# macplus.net
KiCad netlist of a schematic drawn in EAGLE
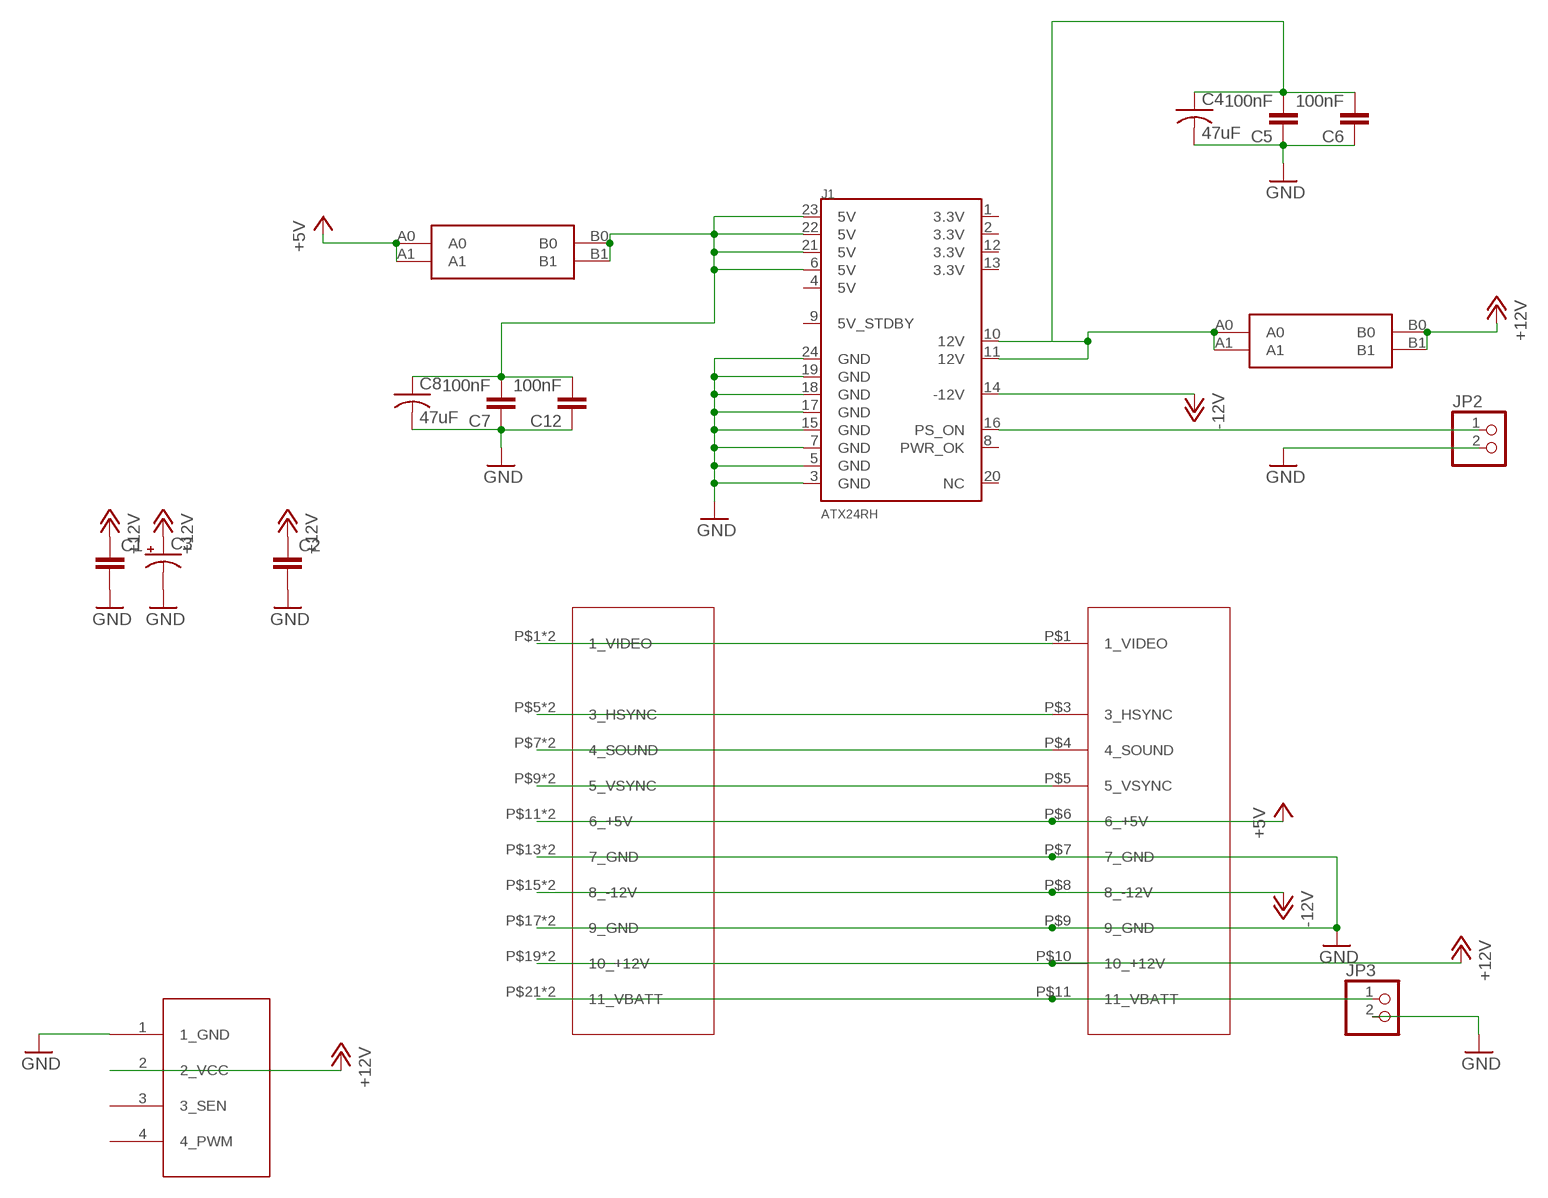
[diagram p0: schematic, sheet 1]

(export (version "E")
  (design (tool "Eeschema 10.0.6"))
  (components
    (comp (ref "C1")
      (value "C5/2.5")
      (footprint "eagle-import:C5B2.5")
      (libsource (lib "eagle-import") (part "C5/2.5"))
    )
    (comp (ref "C2")
      (value "C5/2.5")
      (footprint "eagle-import:C5B2.5")
      (libsource (lib "eagle-import") (part "C5/2.5"))
    )
    (comp (ref "C3")
      (value "CPOL-USE3.5-8")
      (footprint "eagle-import:E3,5-8")
      (libsource (lib "eagle-import") (part "CPOL-USE3.5-8"))
    )
    (comp (ref "C4")
      (value "47uF")
      (footprint "eagle-import:C1210")
      (libsource (lib "eagle-import") (part "C-USC1210"))
    )
    (comp (ref "C5")
      (value "100nF")
      (footprint "eagle-import:0805@1")
      (libsource (lib "eagle-import") (part "CAP0805"))
    )
    (comp (ref "C6")
      (value "100nF")
      (footprint "eagle-import:0805@1")
      (libsource (lib "eagle-import") (part "CAP0805"))
    )
    (comp (ref "C7")
      (value "100nF")
      (footprint "eagle-import:0805@1")
      (libsource (lib "eagle-import") (part "CAP0805"))
    )
    (comp (ref "C8")
      (value "47uF")
      (footprint "eagle-import:C1210")
      (libsource (lib "eagle-import") (part "C-USC1210"))
    )
    (comp (ref "C12")
      (value "100nF")
      (footprint "eagle-import:0805@1")
      (libsource (lib "eagle-import") (part "CAP0805"))
    )
    (comp (ref "J1")
      (value "ATX24RH")
      (footprint "eagle-import:ATX24_STRAIGHT")
      (libsource (lib "eagle-import") (part "ATX24RH"))
    )
    (comp (ref "JP1")
      (value "4PIN_FAN")
      (footprint "eagle-import:1X04")
      (libsource (lib "eagle-import") (part "4PIN_FAN"))
    )
    (comp (ref "JP2")
      (value "PINHD-1X2")
      (footprint "eagle-import:1X02")
      (libsource (lib "eagle-import") (part "PINHD-1X2"))
    )
    (comp (ref "JP3")
      (value "PINHD-1X2")
      (footprint "eagle-import:1X02")
      (libsource (lib "eagle-import") (part "PINHD-1X2"))
    )
    (comp (ref "U$1")
      (value "MACPLUS")
      (footprint "eagle-import:396_10P")
      (libsource (lib "eagle-import") (part "MACPLUS"))
    )
    (comp (ref "U$2")
      (value "CAR_FUSE_HOLDER3IN1")
      (footprint "eagle-import:FUSE_HOLDER_3IN1")
      (libsource (lib "eagle-import") (part "CAR_FUSE_HOLDER3IN1"))
    )
    (comp (ref "U$3")
      (value "3.96_FEM")
      (footprint "eagle-import:3.96_FEMALE_GAP")
      (libsource (lib "eagle-import") (part "3.96_FEM"))
    )
    (comp (ref "U$8")
      (value "CAR_FUSE_HOLDER3IN1")
      (footprint "eagle-import:FUSE_HOLDER_3IN1")
      (libsource (lib "eagle-import") (part "CAR_FUSE_HOLDER3IN1"))
    )
  )
  (nets
    (net (code "1") (name "+5V") (class "Default")
      (node (ref "U$1") (pin "P$6") (pinfunction "6_+5V_P$6") (pintype "bidirectional"))
      (node (ref "U$3") (pin "P$11") (pinfunction "6_+5V_P$11") (pintype "bidirectional"))
      (node (ref "U$3") (pin "P$12") (pinfunction "6_+5V_P$12") (pintype "bidirectional"))
      (node (ref "U$8") (pin "A0") (pinfunction "A0_A0") (pintype "bidirectional"))
      (node (ref "U$8") (pin "A1") (pinfunction "A1_A1") (pintype "bidirectional"))
    )
    (net (code "2") (name "+12V") (class "Default")
      (node (ref "C1") (pin "1") (pinfunction "1_1") (pintype "passive"))
      (node (ref "C2") (pin "1") (pinfunction "1_1") (pintype "passive"))
      (node (ref "C3") (pin "+") (pinfunction "+_+") (pintype "passive"))
      (node (ref "JP1") (pin "2") (pinfunction "2_VCC_2") (pintype "passive"))
      (node (ref "U$1") (pin "P$10") (pinfunction "10_+12V_P$10") (pintype "bidirectional"))
      (node (ref "U$2") (pin "B0") (pinfunction "B0_B0") (pintype "bidirectional"))
      (node (ref "U$2") (pin "B1") (pinfunction "B1_B1") (pintype "bidirectional"))
      (node (ref "U$3") (pin "P$19") (pinfunction "10_+12V_P$19") (pintype "bidirectional"))
      (node (ref "U$3") (pin "P$20") (pinfunction "10_+12V_P$20") (pintype "bidirectional"))
    )
    (net (code "3") (name "-12V") (class "Default")
      (node (ref "J1") (pin "14") (pinfunction "-12V_14") (pintype "bidirectional"))
      (node (ref "U$1") (pin "P$8") (pinfunction "8_-12V_P$8") (pintype "bidirectional"))
      (node (ref "U$3") (pin "P$15") (pinfunction "8_-12V_P$15") (pintype "bidirectional"))
      (node (ref "U$3") (pin "P$16") (pinfunction "8_-12V_P$16") (pintype "bidirectional"))
    )
    (net (code "4") (name "GND") (class "Default")
      (node (ref "C1") (pin "2") (pinfunction "2_2") (pintype "passive"))
      (node (ref "C12") (pin "1") (pinfunction "1_1") (pintype "passive"))
      (node (ref "C2") (pin "2") (pinfunction "2_2") (pintype "passive"))
      (node (ref "C3") (pin "-") (pinfunction "-_-") (pintype "passive"))
      (node (ref "C4") (pin "2") (pinfunction "2_2") (pintype "passive"))
      (node (ref "C5") (pin "1") (pinfunction "1_1") (pintype "passive"))
      (node (ref "C6") (pin "1") (pinfunction "1_1") (pintype "passive"))
      (node (ref "C7") (pin "1") (pinfunction "1_1") (pintype "passive"))
      (node (ref "C8") (pin "2") (pinfunction "2_2") (pintype "passive"))
      (node (ref "J1") (pin "15") (pinfunction "GND_15") (pintype "bidirectional"))
      (node (ref "J1") (pin "17") (pinfunction "GND_17") (pintype "bidirectional"))
      (node (ref "J1") (pin "18") (pinfunction "GND_18") (pintype "bidirectional"))
      (node (ref "J1") (pin "19") (pinfunction "GND_19") (pintype "bidirectional"))
      (node (ref "J1") (pin "24") (pinfunction "GND_24") (pintype "bidirectional"))
      (node (ref "J1") (pin "3") (pinfunction "GND_3") (pintype "bidirectional"))
      (node (ref "J1") (pin "5") (pinfunction "GND_5") (pintype "bidirectional"))
      (node (ref "J1") (pin "7") (pinfunction "GND_7") (pintype "bidirectional"))
      (node (ref "JP1") (pin "1") (pinfunction "1_GND_1") (pintype "passive"))
      (node (ref "JP2") (pin "2") (pinfunction "2_2") (pintype "passive"))
      (node (ref "JP3") (pin "2") (pinfunction "2_2") (pintype "passive"))
      (node (ref "U$1") (pin "P$7") (pinfunction "7_GND_P$7") (pintype "bidirectional"))
      (node (ref "U$1") (pin "P$9") (pinfunction "9_GND_P$9") (pintype "bidirectional"))
      (node (ref "U$3") (pin "P$13") (pinfunction "7_GND_P$13") (pintype "bidirectional"))
      (node (ref "U$3") (pin "P$14") (pinfunction "7_GND_P$14") (pintype "bidirectional"))
      (node (ref "U$3") (pin "P$17") (pinfunction "9_GND_P$17") (pintype "bidirectional"))
      (node (ref "U$3") (pin "P$18") (pinfunction "9_GND_P$18") (pintype "bidirectional"))
    )
    (net (code "5") (name "Net-(C4-Pad1)") (class "Default")
      (node (ref "C4") (pin "1") (pinfunction "1_1") (pintype "passive"))
      (node (ref "C5") (pin "2") (pinfunction "2_2") (pintype "passive"))
      (node (ref "C6") (pin "2") (pinfunction "2_2") (pintype "passive"))
      (node (ref "J1") (pin "10") (pinfunction "12V_10") (pintype "bidirectional"))
      (node (ref "J1") (pin "11") (pinfunction "12V_11") (pintype "bidirectional"))
      (node (ref "U$2") (pin "A0") (pinfunction "A0_A0") (pintype "bidirectional"))
      (node (ref "U$2") (pin "A1") (pinfunction "A1_A1") (pintype "bidirectional"))
    )
    (net (code "6") (name "Net-(C12-Pad2)") (class "Default")
      (node (ref "C12") (pin "2") (pinfunction "2_2") (pintype "passive"))
      (node (ref "C7") (pin "2") (pinfunction "2_2") (pintype "passive"))
      (node (ref "C8") (pin "1") (pinfunction "1_1") (pintype "passive"))
      (node (ref "J1") (pin "21") (pinfunction "5V_21") (pintype "bidirectional"))
      (node (ref "J1") (pin "22") (pinfunction "5V_22") (pintype "bidirectional"))
      (node (ref "J1") (pin "23") (pinfunction "5V_23") (pintype "bidirectional"))
      (node (ref "J1") (pin "6") (pinfunction "5V_6") (pintype "bidirectional"))
      (node (ref "U$8") (pin "B0") (pinfunction "B0_B0") (pintype "bidirectional"))
      (node (ref "U$8") (pin "B1") (pinfunction "B1_B1") (pintype "bidirectional"))
    )
    (net (code "7") (name "Net-(J1-PS_ON)") (class "Default")
      (node (ref "J1") (pin "16") (pinfunction "PS_ON_16") (pintype "bidirectional"))
      (node (ref "JP2") (pin "1") (pinfunction "1_1") (pintype "passive"))
    )
    (net (code "8") (name "Net-(U$1-1_VIDEO)") (class "Default")
      (node (ref "U$1") (pin "P$1") (pinfunction "1_VIDEO_P$1") (pintype "bidirectional"))
      (node (ref "U$3") (pin "P$1") (pinfunction "1_VIDEO_P$1") (pintype "bidirectional"))
      (node (ref "U$3") (pin "P$2") (pinfunction "1_VIDEO_P$2") (pintype "bidirectional"))
    )
    (net (code "9") (name "Net-(U$1-3_HSYNC)") (class "Default")
      (node (ref "U$1") (pin "P$3") (pinfunction "3_HSYNC_P$3") (pintype "bidirectional"))
      (node (ref "U$3") (pin "P$5") (pinfunction "3_HSYNC_P$5") (pintype "bidirectional"))
      (node (ref "U$3") (pin "P$6") (pinfunction "3_HSYNC_P$6") (pintype "bidirectional"))
    )
    (net (code "10") (name "Net-(U$1-4_SOUND)") (class "Default")
      (node (ref "U$1") (pin "P$4") (pinfunction "4_SOUND_P$4") (pintype "bidirectional"))
      (node (ref "U$3") (pin "P$7") (pinfunction "4_SOUND_P$7") (pintype "bidirectional"))
      (node (ref "U$3") (pin "P$8") (pinfunction "4_SOUND_P$8") (pintype "bidirectional"))
    )
    (net (code "11") (name "Net-(U$1-5_VSYNC)") (class "Default")
      (node (ref "U$1") (pin "P$5") (pinfunction "5_VSYNC_P$5") (pintype "bidirectional"))
      (node (ref "U$3") (pin "P$10") (pinfunction "5_VSYNC_P$10") (pintype "bidirectional"))
      (node (ref "U$3") (pin "P$9") (pinfunction "5_VSYNC_P$9") (pintype "bidirectional"))
    )
    (net (code "12") (name "Net-(U$1-11_VBATT)") (class "Default")
      (node (ref "JP3") (pin "1") (pinfunction "1_1") (pintype "passive"))
      (node (ref "U$1") (pin "P$11") (pinfunction "11_VBATT_P$11") (pintype "bidirectional"))
      (node (ref "U$3") (pin "P$21") (pinfunction "11_VBATT_P$21") (pintype "bidirectional"))
      (node (ref "U$3") (pin "P$22") (pinfunction "11_VBATT_P$22") (pintype "bidirectional"))
    )
    (net (code "13") (name "unconnected-(J1-3.3V-Pad1)") (class "Default")
      (node (ref "J1") (pin "1") (pinfunction "3.3V_1") (pintype "bidirectional"))
    )
    (net (code "14") (name "unconnected-(J1-3.3V-Pad2)") (class "Default")
      (node (ref "J1") (pin "2") (pinfunction "3.3V_2") (pintype "bidirectional"))
    )
    (net (code "15") (name "unconnected-(J1-3.3V-Pad12)") (class "Default")
      (node (ref "J1") (pin "12") (pinfunction "3.3V_12") (pintype "bidirectional"))
    )
    (net (code "16") (name "unconnected-(J1-3.3V-Pad13)") (class "Default")
      (node (ref "J1") (pin "13") (pinfunction "3.3V_13") (pintype "bidirectional"))
    )
    (net (code "17") (name "unconnected-(J1-5V-Pad4)") (class "Default")
      (node (ref "J1") (pin "4") (pinfunction "5V_4") (pintype "bidirectional"))
    )
    (net (code "18") (name "unconnected-(J1-5V_STDBY-Pad9)") (class "Default")
      (node (ref "J1") (pin "9") (pinfunction "5V_STDBY_9") (pintype "bidirectional"))
    )
    (net (code "19") (name "unconnected-(J1-NC-Pad20)") (class "Default")
      (node (ref "J1") (pin "20") (pinfunction "NC_20") (pintype "bidirectional"))
    )
    (net (code "20") (name "unconnected-(J1-PWR_OK-Pad8)") (class "Default")
      (node (ref "J1") (pin "8") (pinfunction "PWR_OK_8") (pintype "bidirectional"))
    )
    (net (code "21") (name "unconnected-(JP1-3_SEN-Pad3)") (class "Default")
      (node (ref "JP1") (pin "3") (pinfunction "3_SEN_3") (pintype "passive"))
    )
    (net (code "22") (name "unconnected-(JP1-4_PWM-Pad4)") (class "Default")
      (node (ref "JP1") (pin "4") (pinfunction "4_PWM_4") (pintype "passive"))
    )
  )
)
